# PCB-SDB-1x4.net
KiCad netlist of a schematic drawn in EAGLE
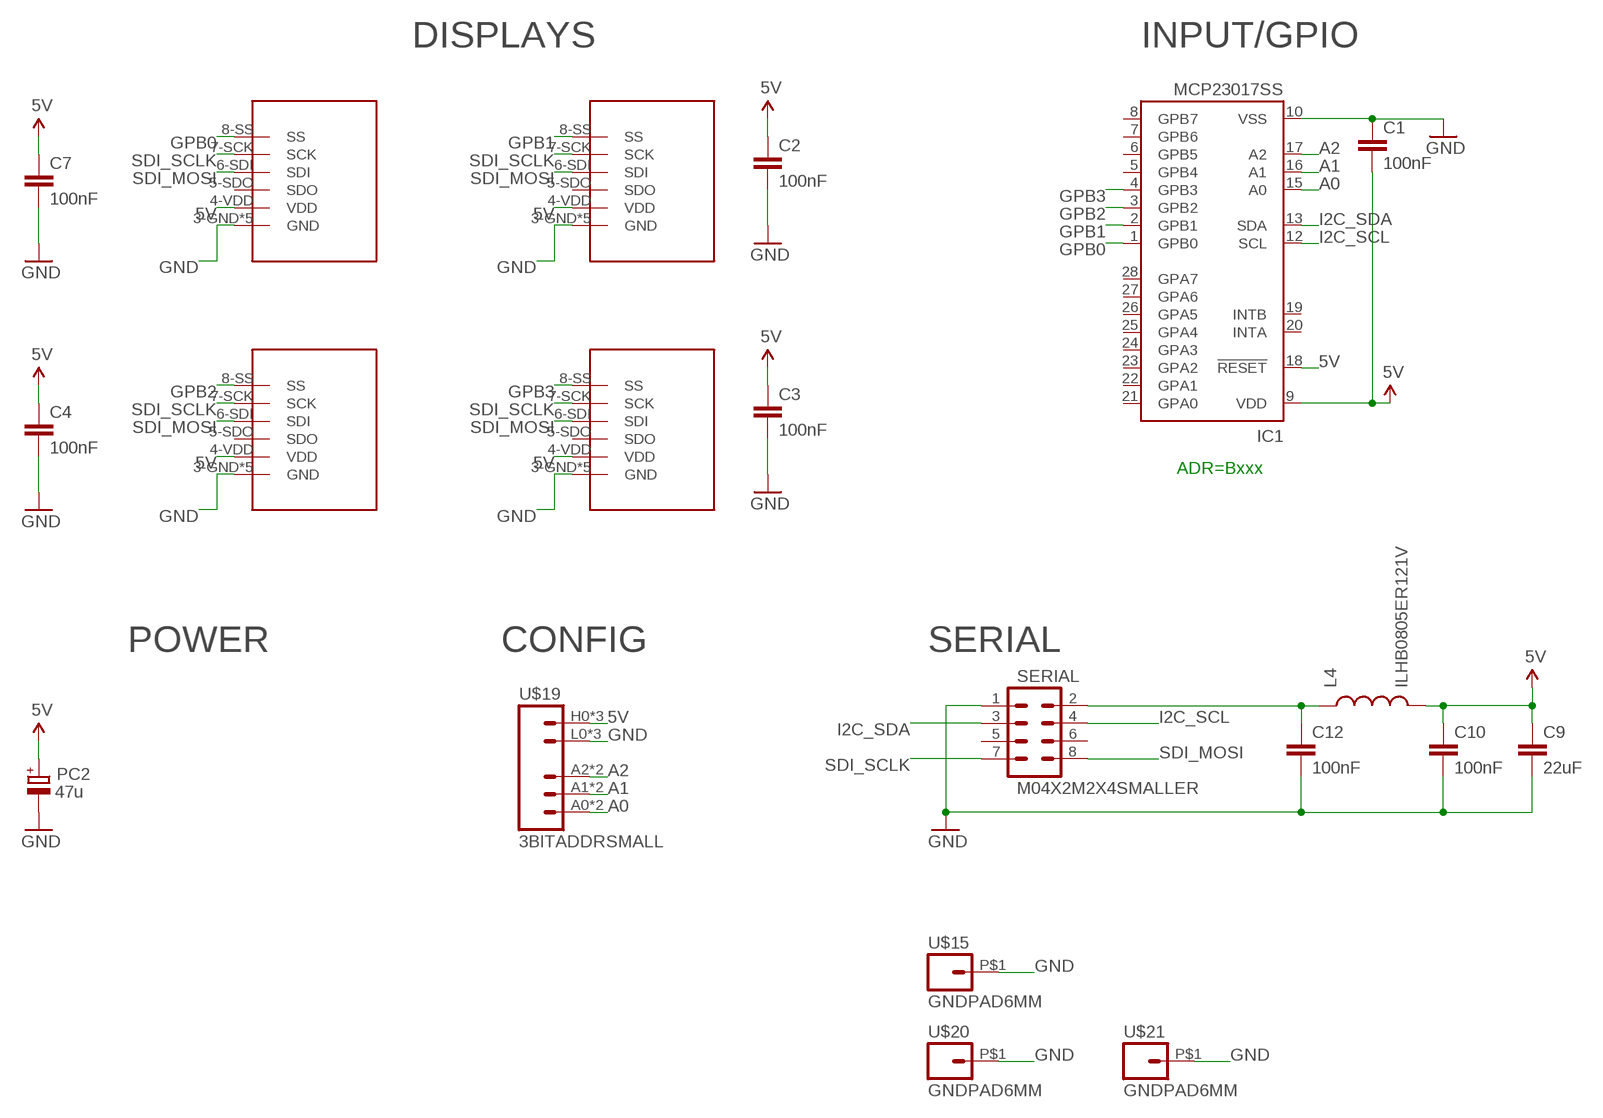
[diagram p0: schematic, sheet 1]

(export (version "E")
  (design (tool "Eeschema 10.0.6"))
  (components
    (comp (ref "C1")
      (value "100nF")
      (footprint "eagle-import:0603-CAP")
      (libsource (lib "eagle-import") (part "CAP0603-CAP"))
    )
    (comp (ref "C2")
      (value "100nF")
      (footprint "eagle-import:0603-CAP")
      (libsource (lib "eagle-import") (part "CAP0603-CAP"))
    )
    (comp (ref "C3")
      (value "100nF")
      (footprint "eagle-import:0603-CAP")
      (libsource (lib "eagle-import") (part "CAP0603-CAP"))
    )
    (comp (ref "C4")
      (value "100nF")
      (footprint "eagle-import:0603-CAP")
      (libsource (lib "eagle-import") (part "CAP0603-CAP"))
    )
    (comp (ref "C7")
      (value "100nF")
      (footprint "eagle-import:0603-CAP")
      (libsource (lib "eagle-import") (part "CAP0603-CAP"))
    )
    (comp (ref "C9")
      (value "22uF")
      (footprint "eagle-import:0805")
      (libsource (lib "eagle-import") (part "CAP0805"))
    )
    (comp (ref "C10")
      (value "100nF")
      (footprint "eagle-import:0603-CAP")
      (libsource (lib "eagle-import") (part "CAP0603-CAP"))
    )
    (comp (ref "C12")
      (value "100nF")
      (footprint "eagle-import:0603-CAP")
      (libsource (lib "eagle-import") (part "CAP0603-CAP"))
    )
    (comp (ref "IC1")
      (value "MCP23017SS")
      (footprint "eagle-import:SSOP28")
      (fields
        (field (name "MF") "MICROCHIP")
        (field (name "MPN") "MCP23017-E/SS")
        (field (name "MPN_1") "MCP23017-E/SS")
        (field (name "OC_FARNELL") "1467674")
        (field (name "OC_NEWARK") "31K2960")
      )
      (libsource (lib "eagle-import") (part "MCP23017SS"))
    )
    (comp (ref "L4")
      (value "ILHB0805ER121V")
      (footprint "eagle-import:0805")
      (libsource (lib "eagle-import") (part "INDUCTOR0805"))
    )
    (comp (ref "PC2")
      (value "47u")
      (footprint "eagle-import:PANASONIC_D")
      (libsource (lib "eagle-import") (part "CPOL-EUD"))
    )
    (comp (ref "SERIAL")
      (value "M04X2M2X4SMALLER")
      (footprint "eagle-import:M2X4SMALLER")
      (libsource (lib "eagle-import") (part "M04X2M2X4SMALLER"))
    )
    (comp (ref "SSW1")
      (value "SMART_DISPLAY")
      (footprint "eagle-import:SMART_DISPLAY")
      (libsource (lib "eagle-import") (part "SMART_DISPLAY"))
    )
    (comp (ref "SSW2")
      (value "SMART_DISPLAY")
      (footprint "eagle-import:SMART_DISPLAY")
      (libsource (lib "eagle-import") (part "SMART_DISPLAY"))
    )
    (comp (ref "SSW3")
      (value "SMART_DISPLAY")
      (footprint "eagle-import:SMART_DISPLAY")
      (libsource (lib "eagle-import") (part "SMART_DISPLAY"))
    )
    (comp (ref "SSW4")
      (value "SMART_DISPLAY")
      (footprint "eagle-import:SMART_DISPLAY")
      (libsource (lib "eagle-import") (part "SMART_DISPLAY"))
    )
    (comp (ref "U$15")
      (value "GNDPAD6MM")
      (footprint "eagle-import:3.2MMPAD6MM")
      (libsource (lib "eagle-import") (part "GNDPAD6MM"))
    )
    (comp (ref "U$19")
      (value "3BITADDRSMALL")
      (footprint "eagle-import:3BITADDR_SMALL")
      (libsource (lib "eagle-import") (part "3BITADDRSMALL"))
    )
    (comp (ref "U$20")
      (value "GNDPAD6MM")
      (footprint "eagle-import:3.2MMPAD6MM")
      (libsource (lib "eagle-import") (part "GNDPAD6MM"))
    )
    (comp (ref "U$21")
      (value "GNDPAD6MM")
      (footprint "eagle-import:3.2MMPAD6MM")
      (libsource (lib "eagle-import") (part "GNDPAD6MM"))
    )
  )
  (nets
    (net (code "1") (name "/A0") (class "Default")
      (node (ref "IC1") (pin "15") (pinfunction "A0_15") (pintype "input"))
      (node (ref "U$19") (pin "A0") (pinfunction "A0_A0") (pintype "passive"))
      (node (ref "U$19") (pin "AS0") (pinfunction "A0_AS0") (pintype "passive"))
    )
    (net (code "2") (name "/A1") (class "Default")
      (node (ref "IC1") (pin "16") (pinfunction "A1_16") (pintype "input"))
      (node (ref "U$19") (pin "A1") (pinfunction "A1_A1") (pintype "passive"))
      (node (ref "U$19") (pin "AS1") (pinfunction "A1_AS1") (pintype "passive"))
    )
    (net (code "3") (name "/A2") (class "Default")
      (node (ref "IC1") (pin "17") (pinfunction "A2_17") (pintype "input"))
      (node (ref "U$19") (pin "A2") (pinfunction "A2_A2") (pintype "passive"))
      (node (ref "U$19") (pin "AS2") (pinfunction "A2_AS2") (pintype "passive"))
    )
    (net (code "4") (name "/GPB0") (class "Default")
      (node (ref "IC1") (pin "1") (pinfunction "GPB0_1") (pintype "bidirectional"))
      (node (ref "SSW1") (pin "8-SS") (pinfunction "SS_8-SS") (pintype "bidirectional"))
    )
    (net (code "5") (name "/GPB1") (class "Default")
      (node (ref "IC1") (pin "2") (pinfunction "GPB1_2") (pintype "bidirectional"))
      (node (ref "SSW2") (pin "8-SS") (pinfunction "SS_8-SS") (pintype "bidirectional"))
    )
    (net (code "6") (name "/GPB2") (class "Default")
      (node (ref "IC1") (pin "3") (pinfunction "GPB2_3") (pintype "bidirectional"))
      (node (ref "SSW3") (pin "8-SS") (pinfunction "SS_8-SS") (pintype "bidirectional"))
    )
    (net (code "7") (name "/GPB3") (class "Default")
      (node (ref "IC1") (pin "4") (pinfunction "GPB3_4") (pintype "bidirectional"))
      (node (ref "SSW4") (pin "8-SS") (pinfunction "SS_8-SS") (pintype "bidirectional"))
    )
    (net (code "8") (name "/I2C_SCL") (class "Default")
      (node (ref "IC1") (pin "12") (pinfunction "SCL_12") (pintype "input"))
      (node (ref "SERIAL") (pin "4") (pinfunction "4_4") (pintype "passive"))
    )
    (net (code "9") (name "/I2C_SDA") (class "Default")
      (node (ref "IC1") (pin "13") (pinfunction "SDA_13") (pintype "bidirectional"))
      (node (ref "SERIAL") (pin "3") (pinfunction "3_3") (pintype "passive"))
    )
    (net (code "10") (name "/SDI_MOSI") (class "Default")
      (node (ref "SERIAL") (pin "8") (pinfunction "8_8") (pintype "passive"))
      (node (ref "SSW1") (pin "6-SDI") (pinfunction "SDI_6-SDI") (pintype "bidirectional"))
      (node (ref "SSW2") (pin "6-SDI") (pinfunction "SDI_6-SDI") (pintype "bidirectional"))
      (node (ref "SSW3") (pin "6-SDI") (pinfunction "SDI_6-SDI") (pintype "bidirectional"))
      (node (ref "SSW4") (pin "6-SDI") (pinfunction "SDI_6-SDI") (pintype "bidirectional"))
    )
    (net (code "11") (name "/SDI_SCLK") (class "Default")
      (node (ref "SERIAL") (pin "7") (pinfunction "7_7") (pintype "passive"))
      (node (ref "SSW1") (pin "7-SCK") (pinfunction "SCK_7-SCK") (pintype "bidirectional"))
      (node (ref "SSW2") (pin "7-SCK") (pinfunction "SCK_7-SCK") (pintype "bidirectional"))
      (node (ref "SSW3") (pin "7-SCK") (pinfunction "SCK_7-SCK") (pintype "bidirectional"))
      (node (ref "SSW4") (pin "7-SCK") (pinfunction "SCK_7-SCK") (pintype "bidirectional"))
    )
    (net (code "12") (name "5V") (class "Default")
      (node (ref "C1") (pin "2") (pinfunction "2_2") (pintype "passive"))
      (node (ref "C10") (pin "1") (pinfunction "1_1") (pintype "passive"))
      (node (ref "C2") (pin "1") (pinfunction "1_1") (pintype "passive"))
      (node (ref "C3") (pin "1") (pinfunction "1_1") (pintype "passive"))
      (node (ref "C4") (pin "1") (pinfunction "1_1") (pintype "passive"))
      (node (ref "C7") (pin "1") (pinfunction "1_1") (pintype "passive"))
      (node (ref "C9") (pin "1") (pinfunction "1_1") (pintype "passive"))
      (node (ref "IC1") (pin "18") (pinfunction "~{RESET}_18") (pintype "input"))
      (node (ref "IC1") (pin "9") (pinfunction "VDD_9") (pintype "power_in"))
      (node (ref "L4") (pin "2") (pinfunction "2_2") (pintype "passive"))
      (node (ref "PC2") (pin "+") (pinfunction "+_+") (pintype "passive"))
      (node (ref "SSW1") (pin "4-VDD") (pinfunction "VDD_4-VDD") (pintype "bidirectional"))
      (node (ref "SSW2") (pin "4-VDD") (pinfunction "VDD_4-VDD") (pintype "bidirectional"))
      (node (ref "SSW3") (pin "4-VDD") (pinfunction "VDD_4-VDD") (pintype "bidirectional"))
      (node (ref "SSW4") (pin "4-VDD") (pinfunction "VDD_4-VDD") (pintype "bidirectional"))
      (node (ref "U$19") (pin "H0") (pinfunction "VCC_H0") (pintype "passive"))
      (node (ref "U$19") (pin "H1") (pinfunction "VCC_H1") (pintype "passive"))
      (node (ref "U$19") (pin "H2") (pinfunction "VCC_H2") (pintype "passive"))
    )
    (net (code "13") (name "GND") (class "Default")
      (node (ref "C1") (pin "1") (pinfunction "1_1") (pintype "passive"))
      (node (ref "C10") (pin "2") (pinfunction "2_2") (pintype "passive"))
      (node (ref "C12") (pin "2") (pinfunction "2_2") (pintype "passive"))
      (node (ref "C2") (pin "2") (pinfunction "2_2") (pintype "passive"))
      (node (ref "C3") (pin "2") (pinfunction "2_2") (pintype "passive"))
      (node (ref "C4") (pin "2") (pinfunction "2_2") (pintype "passive"))
      (node (ref "C7") (pin "2") (pinfunction "2_2") (pintype "passive"))
      (node (ref "C9") (pin "2") (pinfunction "2_2") (pintype "passive"))
      (node (ref "IC1") (pin "10") (pinfunction "VSS_10") (pintype "power_in"))
      (node (ref "PC2") (pin "-") (pinfunction "-_-") (pintype "passive"))
      (node (ref "SERIAL") (pin "1") (pinfunction "1_1") (pintype "passive"))
      (node (ref "SSW1") (pin "3-GND") (pinfunction "GND_3-GND") (pintype "bidirectional"))
      (node (ref "SSW1") (pin "P$1") (pinfunction "GND_P$1") (pintype "bidirectional"))
      (node (ref "SSW1") (pin "P$2") (pinfunction "GND_P$2") (pintype "bidirectional"))
      (node (ref "SSW1") (pin "P$3") (pinfunction "GND_P$3") (pintype "bidirectional"))
      (node (ref "SSW1") (pin "P$4") (pinfunction "GND_P$4") (pintype "bidirectional"))
      (node (ref "SSW2") (pin "3-GND") (pinfunction "GND_3-GND") (pintype "bidirectional"))
      (node (ref "SSW2") (pin "P$1") (pinfunction "GND_P$1") (pintype "bidirectional"))
      (node (ref "SSW2") (pin "P$2") (pinfunction "GND_P$2") (pintype "bidirectional"))
      (node (ref "SSW2") (pin "P$3") (pinfunction "GND_P$3") (pintype "bidirectional"))
      (node (ref "SSW2") (pin "P$4") (pinfunction "GND_P$4") (pintype "bidirectional"))
      (node (ref "SSW3") (pin "3-GND") (pinfunction "GND_3-GND") (pintype "bidirectional"))
      (node (ref "SSW3") (pin "P$1") (pinfunction "GND_P$1") (pintype "bidirectional"))
      (node (ref "SSW3") (pin "P$2") (pinfunction "GND_P$2") (pintype "bidirectional"))
      (node (ref "SSW3") (pin "P$3") (pinfunction "GND_P$3") (pintype "bidirectional"))
      (node (ref "SSW3") (pin "P$4") (pinfunction "GND_P$4") (pintype "bidirectional"))
      (node (ref "SSW4") (pin "3-GND") (pinfunction "GND_3-GND") (pintype "bidirectional"))
      (node (ref "SSW4") (pin "P$1") (pinfunction "GND_P$1") (pintype "bidirectional"))
      (node (ref "SSW4") (pin "P$2") (pinfunction "GND_P$2") (pintype "bidirectional"))
      (node (ref "SSW4") (pin "P$3") (pinfunction "GND_P$3") (pintype "bidirectional"))
      (node (ref "SSW4") (pin "P$4") (pinfunction "GND_P$4") (pintype "bidirectional"))
      (node (ref "U$15") (pin "P$1") (pinfunction "1_P$1") (pintype "passive"))
      (node (ref "U$19") (pin "L0") (pinfunction "GND_L0") (pintype "passive"))
      (node (ref "U$19") (pin "L1") (pinfunction "GND_L1") (pintype "passive"))
      (node (ref "U$19") (pin "L2") (pinfunction "GND_L2") (pintype "passive"))
      (node (ref "U$20") (pin "P$1") (pinfunction "1_P$1") (pintype "passive"))
      (node (ref "U$21") (pin "P$1") (pinfunction "1_P$1") (pintype "passive"))
    )
    (net (code "14") (name "Net-(C12-Pad1)") (class "Default")
      (node (ref "C12") (pin "1") (pinfunction "1_1") (pintype "passive"))
      (node (ref "L4") (pin "1") (pinfunction "1_1") (pintype "passive"))
      (node (ref "SERIAL") (pin "2") (pinfunction "2_2") (pintype "passive"))
    )
    (net (code "15") (name "unconnected-(IC1-GPA0-Pad21)") (class "Default")
      (node (ref "IC1") (pin "21") (pinfunction "GPA0_21") (pintype "bidirectional"))
    )
    (net (code "16") (name "unconnected-(IC1-GPA1-Pad22)") (class "Default")
      (node (ref "IC1") (pin "22") (pinfunction "GPA1_22") (pintype "bidirectional"))
    )
    (net (code "17") (name "unconnected-(IC1-GPA2-Pad23)") (class "Default")
      (node (ref "IC1") (pin "23") (pinfunction "GPA2_23") (pintype "bidirectional"))
    )
    (net (code "18") (name "unconnected-(IC1-GPA3-Pad24)") (class "Default")
      (node (ref "IC1") (pin "24") (pinfunction "GPA3_24") (pintype "bidirectional"))
    )
    (net (code "19") (name "unconnected-(IC1-GPA4-Pad25)") (class "Default")
      (node (ref "IC1") (pin "25") (pinfunction "GPA4_25") (pintype "bidirectional"))
    )
    (net (code "20") (name "unconnected-(IC1-GPA5-Pad26)") (class "Default")
      (node (ref "IC1") (pin "26") (pinfunction "GPA5_26") (pintype "bidirectional"))
    )
    (net (code "21") (name "unconnected-(IC1-GPA6-Pad27)") (class "Default")
      (node (ref "IC1") (pin "27") (pinfunction "GPA6_27") (pintype "bidirectional"))
    )
    (net (code "22") (name "unconnected-(IC1-GPA7-Pad28)") (class "Default")
      (node (ref "IC1") (pin "28") (pinfunction "GPA7_28") (pintype "bidirectional"))
    )
    (net (code "23") (name "unconnected-(IC1-GPB4-Pad5)") (class "Default")
      (node (ref "IC1") (pin "5") (pinfunction "GPB4_5") (pintype "bidirectional"))
    )
    (net (code "24") (name "unconnected-(IC1-GPB5-Pad6)") (class "Default")
      (node (ref "IC1") (pin "6") (pinfunction "GPB5_6") (pintype "bidirectional"))
    )
    (net (code "25") (name "unconnected-(IC1-GPB6-Pad7)") (class "Default")
      (node (ref "IC1") (pin "7") (pinfunction "GPB6_7") (pintype "bidirectional"))
    )
    (net (code "26") (name "unconnected-(IC1-GPB7-Pad8)") (class "Default")
      (node (ref "IC1") (pin "8") (pinfunction "GPB7_8") (pintype "bidirectional"))
    )
    (net (code "27") (name "unconnected-(IC1-INTA-Pad20)") (class "Default")
      (node (ref "IC1") (pin "20") (pinfunction "INTA_20") (pintype "output"))
    )
    (net (code "28") (name "unconnected-(IC1-INTB-Pad19)") (class "Default")
      (node (ref "IC1") (pin "19") (pinfunction "INTB_19") (pintype "output"))
    )
    (net (code "29") (name "unconnected-(SERIAL-Pad5)") (class "Default")
      (node (ref "SERIAL") (pin "5") (pinfunction "5_5") (pintype "passive"))
    )
    (net (code "30") (name "unconnected-(SERIAL-Pad6)") (class "Default")
      (node (ref "SERIAL") (pin "6") (pinfunction "6_6") (pintype "passive"))
    )
    (net (code "31") (name "unconnected-(SSW1-SDO-Pad5-SDO)") (class "Default")
      (node (ref "SSW1") (pin "5-SDO") (pinfunction "SDO_5-SDO") (pintype "bidirectional"))
    )
    (net (code "32") (name "unconnected-(SSW2-SDO-Pad5-SDO)") (class "Default")
      (node (ref "SSW2") (pin "5-SDO") (pinfunction "SDO_5-SDO") (pintype "bidirectional"))
    )
    (net (code "33") (name "unconnected-(SSW3-SDO-Pad5-SDO)") (class "Default")
      (node (ref "SSW3") (pin "5-SDO") (pinfunction "SDO_5-SDO") (pintype "bidirectional"))
    )
    (net (code "34") (name "unconnected-(SSW4-SDO-Pad5-SDO)") (class "Default")
      (node (ref "SSW4") (pin "5-SDO") (pinfunction "SDO_5-SDO") (pintype "bidirectional"))
    )
  )
)
